# LED8.net
KiCad netlist of a schematic drawn in Altium Designer
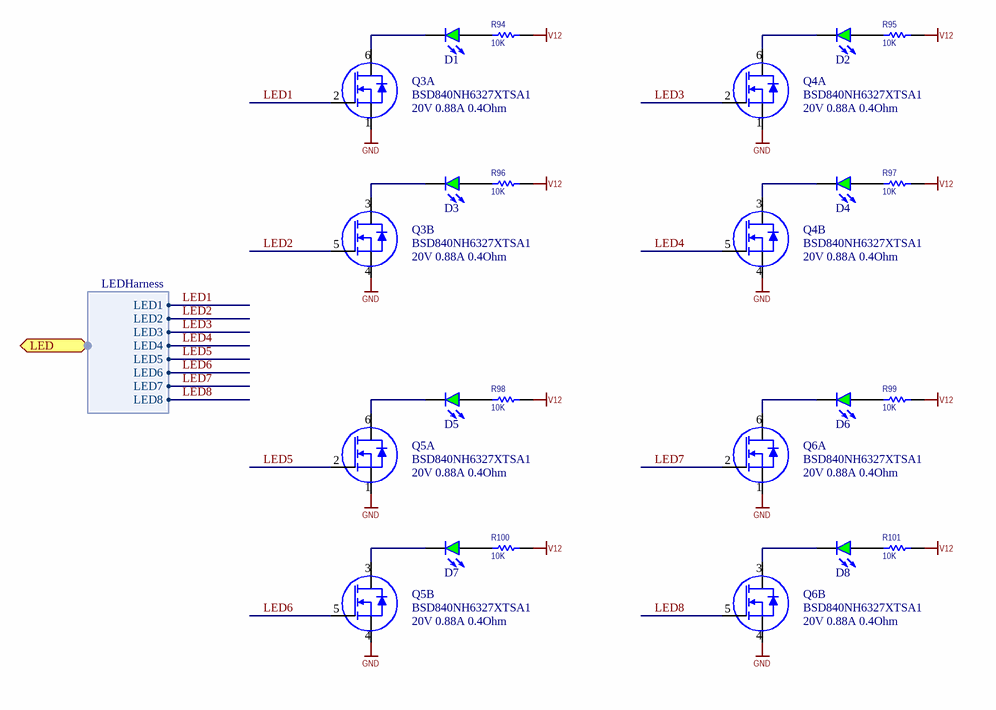
[diagram p0: LED8.SchDoc]

(export (version "E")
  (design (tool "Eeschema 10.0.6"))
  (components
    (comp (ref "D1")
      (value "LED Green 130° 0603")
      (footprint "CAPC1608N-0603")
      (fields (field (name "MFG") "Liteon"))
      (libsource (lib "Kron Library Rev 3") (part "LTST-C191KGKT"))
    )
    (comp (ref "D2")
      (value "LED Green 130° 0603")
      (footprint "CAPC1608N-0603")
      (fields (field (name "MFG") "Liteon"))
      (libsource (lib "Kron Library Rev 3") (part "LTST-C191KGKT"))
    )
    (comp (ref "D3")
      (value "LED Green 130° 0603")
      (footprint "CAPC1608N-0603")
      (fields (field (name "MFG") "Liteon"))
      (libsource (lib "Kron Library Rev 3") (part "LTST-C191KGKT"))
    )
    (comp (ref "D4")
      (value "LED Green 130° 0603")
      (footprint "CAPC1608N-0603")
      (fields (field (name "MFG") "Liteon"))
      (libsource (lib "Kron Library Rev 3") (part "LTST-C191KGKT"))
    )
    (comp (ref "D5")
      (value "LED Green 130° 0603")
      (footprint "CAPC1608N-0603")
      (fields (field (name "MFG") "Liteon"))
      (libsource (lib "Kron Library Rev 3") (part "LTST-C191KGKT"))
    )
    (comp (ref "D6")
      (value "LED Green 130° 0603")
      (footprint "CAPC1608N-0603")
      (fields (field (name "MFG") "Liteon"))
      (libsource (lib "Kron Library Rev 3") (part "LTST-C191KGKT"))
    )
    (comp (ref "D7")
      (value "LED Green 130° 0603")
      (footprint "CAPC1608N-0603")
      (fields (field (name "MFG") "Liteon"))
      (libsource (lib "Kron Library Rev 3") (part "LTST-C191KGKT"))
    )
    (comp (ref "D8")
      (value "LED Green 130° 0603")
      (footprint "CAPC1608N-0603")
      (fields (field (name "MFG") "Liteon"))
      (libsource (lib "Kron Library Rev 3") (part "LTST-C191KGKT"))
    )
    (comp (ref "Q3")
      (value "20V 0.88A 0.4Ohm")
      (footprint "SOT-363")
      (description "Tran N-MOSFET 20V 0.88A Dual Logic Level SOT363")
      (fields (field (name "MFG") "Infineon") (field (name "MFGR P/N") "BSD840NH6327XTSA1"))
      (libsource (lib "infinion") (part "BSD840NH6327XTSA1"))
    )
    (comp (ref "Q4")
      (value "20V 0.88A 0.4Ohm")
      (footprint "SOT-363")
      (description "Tran N-MOSFET 20V 0.88A Dual Logic Level SOT363")
      (fields (field (name "MFG") "Infineon") (field (name "MFGR P/N") "BSD840NH6327XTSA1"))
      (libsource (lib "infinion") (part "BSD840NH6327XTSA1"))
    )
    (comp (ref "Q5")
      (value "20V 0.88A 0.4Ohm")
      (footprint "SOT-363")
      (description "Tran N-MOSFET 20V 0.88A Dual Logic Level SOT363")
      (fields (field (name "MFG") "Infineon") (field (name "MFGR P/N") "BSD840NH6327XTSA1"))
      (libsource (lib "infinion") (part "BSD840NH6327XTSA1"))
    )
    (comp (ref "Q6")
      (value "20V 0.88A 0.4Ohm")
      (footprint "SOT-363")
      (description "Tran N-MOSFET 20V 0.88A Dual Logic Level SOT363")
      (fields (field (name "MFG") "Infineon") (field (name "MFGR P/N") "BSD840NH6327XTSA1"))
      (libsource (lib "infinion") (part "BSD840NH6327XTSA1"))
    )
    (comp (ref "R94")
      (value "10K")
      (footprint "0402")
      (description "Resistor, SMD 0402")
      (fields (field (name "Comment") "RES 0402"))
      (libsource (lib "Graviton") (part "RES 0402"))
    )
    (comp (ref "R95")
      (value "10K")
      (footprint "0402")
      (description "Resistor, SMD 0402")
      (fields (field (name "Comment") "RES 0402"))
      (libsource (lib "Graviton") (part "RES 0402"))
    )
    (comp (ref "R96")
      (value "10K")
      (footprint "0402")
      (description "Resistor, SMD 0402")
      (fields (field (name "Comment") "RES 0402"))
      (libsource (lib "Graviton") (part "RES 0402"))
    )
    (comp (ref "R97")
      (value "10K")
      (footprint "0402")
      (description "Resistor, SMD 0402")
      (fields (field (name "Comment") "RES 0402"))
      (libsource (lib "Graviton") (part "RES 0402"))
    )
    (comp (ref "R98")
      (value "10K")
      (footprint "0402")
      (description "Resistor, SMD 0402")
      (fields (field (name "Comment") "RES 0402"))
      (libsource (lib "Graviton") (part "RES 0402"))
    )
    (comp (ref "R99")
      (value "10K")
      (footprint "0402")
      (description "Resistor, SMD 0402")
      (fields (field (name "Comment") "RES 0402"))
      (libsource (lib "Graviton") (part "RES 0402"))
    )
    (comp (ref "R100")
      (value "10K")
      (footprint "0402")
      (description "Resistor, SMD 0402")
      (fields (field (name "Comment") "RES 0402"))
      (libsource (lib "Graviton") (part "RES 0402"))
    )
    (comp (ref "R101")
      (value "10K")
      (footprint "0402")
      (description "Resistor, SMD 0402")
      (fields (field (name "Comment") "RES 0402"))
      (libsource (lib "Graviton") (part "RES 0402"))
    )
  )
  (nets
    (net (code "2") (name "/LED1") (class "Default")
      (node (ref "Q3") (pin "2") (pinfunction "Gate_1_2") (pintype "passive"))
    )
    (net (code "3") (name "/LED2") (class "Default")
      (node (ref "Q3") (pin "5") (pinfunction "Gate_2_5") (pintype "passive"))
    )
    (net (code "4") (name "/LED3") (class "Default")
      (node (ref "Q4") (pin "2") (pinfunction "Gate_1_2") (pintype "passive"))
    )
    (net (code "5") (name "/LED4") (class "Default")
      (node (ref "Q4") (pin "5") (pinfunction "Gate_2_5") (pintype "passive"))
    )
    (net (code "6") (name "/LED5") (class "Default")
      (node (ref "Q5") (pin "2") (pinfunction "Gate_1_2") (pintype "passive"))
    )
    (net (code "7") (name "/LED6") (class "Default")
      (node (ref "Q5") (pin "5") (pinfunction "Gate_2_5") (pintype "passive"))
    )
    (net (code "8") (name "/LED7") (class "Default")
      (node (ref "Q6") (pin "2") (pinfunction "Gate_1_2") (pintype "passive"))
    )
    (net (code "9") (name "/LED8") (class "Default")
      (node (ref "Q6") (pin "5") (pinfunction "Gate_2_5") (pintype "passive"))
    )
    (net (code "11") (name "GND") (class "Default")
      (node (ref "Q3") (pin "1") (pinfunction "Source_1_1") (pintype "passive"))
      (node (ref "Q3") (pin "4") (pinfunction "Source_2_4") (pintype "passive"))
      (node (ref "Q4") (pin "1") (pinfunction "Source_1_1") (pintype "passive"))
      (node (ref "Q4") (pin "4") (pinfunction "Source_2_4") (pintype "passive"))
      (node (ref "Q5") (pin "1") (pinfunction "Source_1_1") (pintype "passive"))
      (node (ref "Q5") (pin "4") (pinfunction "Source_2_4") (pintype "passive"))
      (node (ref "Q6") (pin "1") (pinfunction "Source_1_1") (pintype "passive"))
      (node (ref "Q6") (pin "4") (pinfunction "Source_2_4") (pintype "passive"))
    )
    (net (code "12") (name "Net-(D1-Anode)") (class "Default")
      (node (ref "D1") (pin "2") (pinfunction "Anode_2") (pintype "passive"))
      (node (ref "R94") (pin "1") (pinfunction "1_1") (pintype "passive"))
    )
    (net (code "13") (name "Net-(D1-Cathode)") (class "Default")
      (node (ref "D1") (pin "1") (pinfunction "Cathode_1") (pintype "passive"))
      (node (ref "Q3") (pin "6") (pinfunction "Drain_1_6") (pintype "passive"))
    )
    (net (code "14") (name "Net-(D2-Anode)") (class "Default")
      (node (ref "D2") (pin "2") (pinfunction "Anode_2") (pintype "passive"))
      (node (ref "R95") (pin "1") (pinfunction "1_1") (pintype "passive"))
    )
    (net (code "15") (name "Net-(D2-Cathode)") (class "Default")
      (node (ref "D2") (pin "1") (pinfunction "Cathode_1") (pintype "passive"))
      (node (ref "Q4") (pin "6") (pinfunction "Drain_1_6") (pintype "passive"))
    )
    (net (code "16") (name "Net-(D3-Anode)") (class "Default")
      (node (ref "D3") (pin "2") (pinfunction "Anode_2") (pintype "passive"))
      (node (ref "R96") (pin "1") (pinfunction "1_1") (pintype "passive"))
    )
    (net (code "17") (name "Net-(D3-Cathode)") (class "Default")
      (node (ref "D3") (pin "1") (pinfunction "Cathode_1") (pintype "passive"))
      (node (ref "Q3") (pin "3") (pinfunction "Drain_2_3") (pintype "passive"))
    )
    (net (code "18") (name "Net-(D4-Anode)") (class "Default")
      (node (ref "D4") (pin "2") (pinfunction "Anode_2") (pintype "passive"))
      (node (ref "R97") (pin "1") (pinfunction "1_1") (pintype "passive"))
    )
    (net (code "19") (name "Net-(D4-Cathode)") (class "Default")
      (node (ref "D4") (pin "1") (pinfunction "Cathode_1") (pintype "passive"))
      (node (ref "Q4") (pin "3") (pinfunction "Drain_2_3") (pintype "passive"))
    )
    (net (code "20") (name "Net-(D5-Anode)") (class "Default")
      (node (ref "D5") (pin "2") (pinfunction "Anode_2") (pintype "passive"))
      (node (ref "R98") (pin "1") (pinfunction "1_1") (pintype "passive"))
    )
    (net (code "21") (name "Net-(D5-Cathode)") (class "Default")
      (node (ref "D5") (pin "1") (pinfunction "Cathode_1") (pintype "passive"))
      (node (ref "Q5") (pin "6") (pinfunction "Drain_1_6") (pintype "passive"))
    )
    (net (code "22") (name "Net-(D6-Anode)") (class "Default")
      (node (ref "D6") (pin "2") (pinfunction "Anode_2") (pintype "passive"))
      (node (ref "R99") (pin "1") (pinfunction "1_1") (pintype "passive"))
    )
    (net (code "23") (name "Net-(D6-Cathode)") (class "Default")
      (node (ref "D6") (pin "1") (pinfunction "Cathode_1") (pintype "passive"))
      (node (ref "Q6") (pin "6") (pinfunction "Drain_1_6") (pintype "passive"))
    )
    (net (code "24") (name "Net-(D7-Anode)") (class "Default")
      (node (ref "D7") (pin "2") (pinfunction "Anode_2") (pintype "passive"))
      (node (ref "R100") (pin "1") (pinfunction "1_1") (pintype "passive"))
    )
    (net (code "25") (name "Net-(D7-Cathode)") (class "Default")
      (node (ref "D7") (pin "1") (pinfunction "Cathode_1") (pintype "passive"))
      (node (ref "Q5") (pin "3") (pinfunction "Drain_2_3") (pintype "passive"))
    )
    (net (code "26") (name "Net-(D8-Anode)") (class "Default")
      (node (ref "D8") (pin "2") (pinfunction "Anode_2") (pintype "passive"))
      (node (ref "R101") (pin "1") (pinfunction "1_1") (pintype "passive"))
    )
    (net (code "27") (name "Net-(D8-Cathode)") (class "Default")
      (node (ref "D8") (pin "1") (pinfunction "Cathode_1") (pintype "passive"))
      (node (ref "Q6") (pin "3") (pinfunction "Drain_2_3") (pintype "passive"))
    )
    (net (code "28") (name "V12") (class "Default")
      (node (ref "R100") (pin "2") (pinfunction "2_2") (pintype "passive"))
      (node (ref "R101") (pin "2") (pinfunction "2_2") (pintype "passive"))
      (node (ref "R94") (pin "2") (pinfunction "2_2") (pintype "passive"))
      (node (ref "R95") (pin "2") (pinfunction "2_2") (pintype "passive"))
      (node (ref "R96") (pin "2") (pinfunction "2_2") (pintype "passive"))
      (node (ref "R97") (pin "2") (pinfunction "2_2") (pintype "passive"))
      (node (ref "R98") (pin "2") (pinfunction "2_2") (pintype "passive"))
      (node (ref "R99") (pin "2") (pinfunction "2_2") (pintype "passive"))
    )
  )
)
